# Voltage_AC.net
KiCad netlist of a schematic drawn in Altium Designer
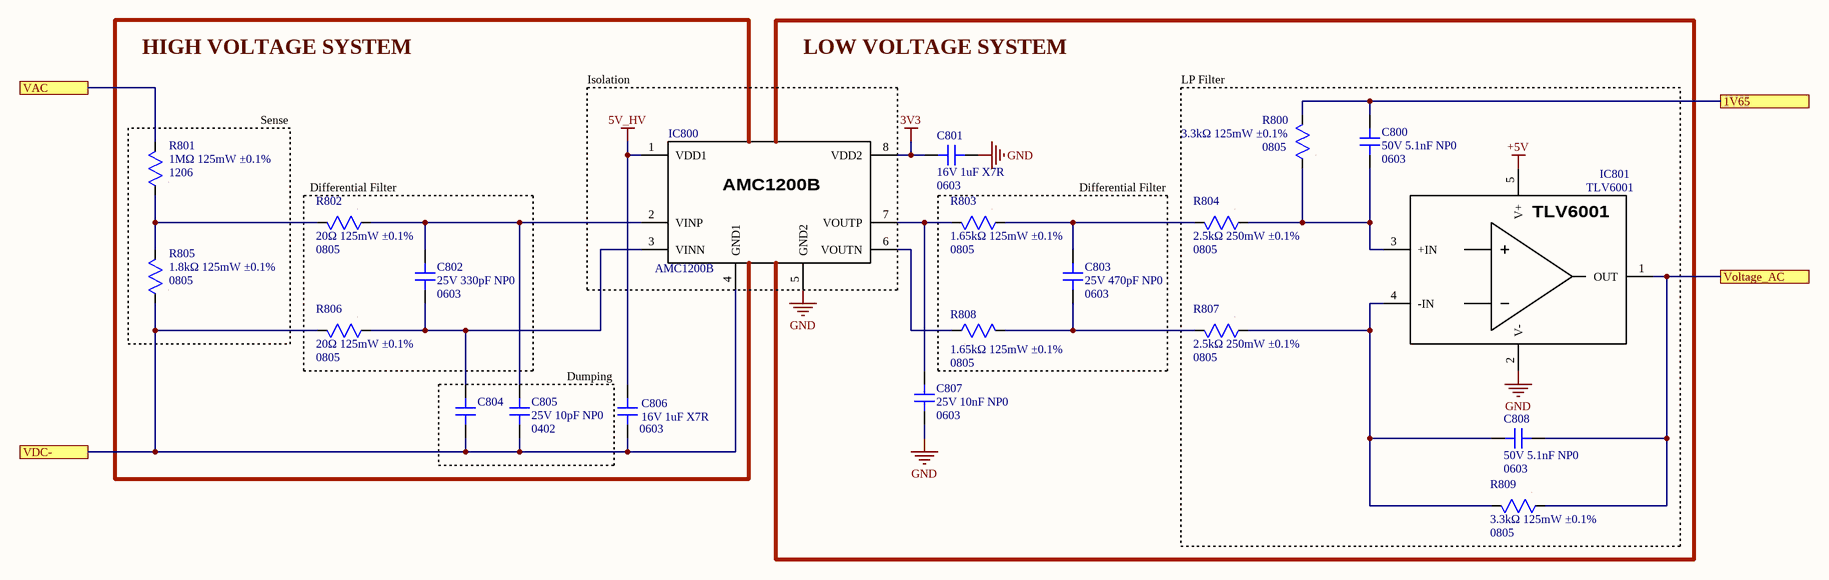
[diagram p0: Voltage_AC.SchDoc]

(export (version "E")
  (design (tool "Eeschema 10.0.6"))
  (components
    (comp (ref "C800")
      (value "50V 5.1nF NP0")
      (footprint "CAP SMD 0603")
      (description "Condensadores de cerámica multicapa (MLCC- SMD/SMT) 50V 5100pF 0603 C0G 1%")
      (fields
        (field (name "PACKAGE") "0603")
        (field (name "MPN") "C0603C512F5GACTU")
        (field (name "MANUFACTURER") "KEMET")
      )
      (libsource (lib "eUSR_Database") (part "CAP non polarized"))
    )
    (comp (ref "C801")
      (value "16V 1uF X7R")
      (footprint "CAP SMD 0603")
      (description "Condensadores de cerámica multicapa (MLCC- SMD/SMT) WCAP-CSGP 1uF 0603 10% 16V MLCC")
      (fields
        (field (name "PACKAGE") "0603")
        (field (name "MPN") "885012206052")
        (field (name "MANUFACTURER") "Wurth Elektronik")
      )
      (libsource (lib "eUSR_Database") (part "CAP non polarized"))
    )
    (comp (ref "C802")
      (value "25V 330pF NP0")
      (footprint "CAP SMD 0603")
      (description "Condensadores de cerámica multicapa (MLCC- SMD/SMT) 0603 330pF 25volts C0G 1%")
      (fields
        (field (name "PACKAGE") "0603")
        (field (name "MPN") "VJ0603A331FXXCW1BC")
        (field (name "MANUFACTURER") "Vishay")
      )
      (libsource (lib "eUSR_Database") (part "CAP non polarized"))
    )
    (comp (ref "C803")
      (value "25V 470pF NP0")
      (footprint "CAP SMD 0603")
      (fields
        (field (name "PACKAGE") "0603")
        (field (name "MPN") "VJ0603D471KCXAJ")
        (field (name "MANUFACTURER") "Vishay")
        (field (name "Comment") "CAP non polarized")
      )
      (libsource (lib "eUSR_Database") (part "CAP non polarized"))
    )
    (comp (ref "C804")
      (value "CAP non polarized")
      (footprint "CAP SMD 0402")
      (description "Condensadores de cerámica multicapa (MLCC- SMD/SMT) 25V 10pF C0G 0402 0. 1pF")
      (fields (field (name "MPN") "04023A100BAT2A") (field (name "MANUFACTURER") "KYOCERA AVX"))
      (libsource (lib "eUSR_Database") (part "CAP non polarized"))
    )
    (comp (ref "C805")
      (value "25V 10pF NP0")
      (footprint "CAP SMD 0402")
      (description "Condensadores de cerámica multicapa (MLCC- SMD/SMT) 25V 10pF C0G 0402 0. 1pF")
      (fields
        (field (name "PACKAGE") "0402")
        (field (name "MPN") "04023A100BAT2A")
        (field (name "MANUFACTURER") "KYOCERA AVX")
      )
      (libsource (lib "eUSR_Database") (part "CAP non polarized"))
    )
    (comp (ref "C806")
      (value "16V 1uF X7R")
      (footprint "CAP SMD 0603")
      (description "Condensadores de cerámica multicapa (MLCC- SMD/SMT) WCAP-CSGP 1uF 0603 10% 16V MLCC")
      (fields
        (field (name "PACKAGE") "0603")
        (field (name "MPN") "885012206052")
        (field (name "MANUFACTURER") "Wurth Elektronik")
      )
      (libsource (lib "eUSR_Database") (part "CAP non polarized"))
    )
    (comp (ref "C807")
      (value "25V 10nF NP0")
      (footprint "CAP SMD 0603")
      (description "Condensadores de cerámica multicapa (MLCC- SMD/SMT) 50V 5100pF 0603 C0G 1%")
      (fields
        (field (name "PACKAGE") "0603")
        (field (name "MPN") "C0603C512F5GACTU")
        (field (name "MANUFACTURER") "KEMET")
      )
      (libsource (lib "eUSR_Database") (part "CAP non polarized"))
    )
    (comp (ref "C808")
      (value "50V 5.1nF NP0")
      (footprint "CAP SMD 0603")
      (description "Condensadores de cerámica multicapa (MLCC- SMD/SMT) 50V 5100pF 0603 C0G 1%")
      (fields
        (field (name "PACKAGE") "0603")
        (field (name "MPN") "C0603C512F5GACTU")
        (field (name "MANUFACTURER") "KEMET")
      )
      (libsource (lib "eUSR_Database") (part "CAP non polarized"))
    )
    (comp (ref "IC800")
      (value "AMC1200B")
      (footprint "AMC1200B")
      (description "Amplificadores de aislamiento 4kV peak Iso Amp A 5 95-AMC1200BDUB A 59 A 595-AMC1200BDUB")
      (fields (field (name "MPN") "AMC1200BDUBR") (field (name "MANUFACTURER") "Texas Instruments"))
      (libsource (lib "eUSR_Database") (part "AMC1200B"))
    )
    (comp (ref "IC801")
      (value "TLV6001")
      (footprint "SOT-23-5")
      (fields (field (name "MPN") "TLV6001UIDBVR") (field (name "MANUFACTURER") "Texas Instruments"))
      (libsource (lib "eUSR_Database") (part "TLV6001"))
    )
    (comp (ref "R800")
      (value "3.3kΩ 125mW ±0.1%")
      (footprint "RES SMD 0805")
      (description "Thin Film Resistors 0805 3.3Kohm 0.1% 15ppm AEC-Q200")
      (fields
        (field (name "PACKAGE") "0805")
        (field (name "MPN") "ERA-6APB332V")
        (field (name "MANUFACTURER") "Panasonic")
      )
      (libsource (lib "eUSR_Database") (part "RES"))
    )
    (comp (ref "R801")
      (value "1MΩ 125mW ±0.1%")
      (footprint "RES SMD 1206")
      (description "Thin Film Resistors CHIP RESISTOR Precision")
      (fields
        (field (name "PACKAGE") "1206")
        (field (name "MPN") "CRT1206-BW-1004ELF")
        (field (name "MANUFACTURER") "Bourns")
      )
      (libsource (lib "eUSR_Database") (part "RES"))
    )
    (comp (ref "R802")
      (value "20Ω 125mW ±0.1%")
      (footprint "RES SMD 0805")
      (description "Thin Film Resistors RP 2A 20R 0.1% 15PPM CUT LENGTH")
      (fields
        (field (name "PACKAGE") "0805")
        (field (name "MPN") "RP73D2A20RBTG")
        (field (name "MANUFACTURER") "TE")
      )
      (libsource (lib "eUSR_Database") (part "RES"))
    )
    (comp (ref "R803")
      (value "1.65kΩ 125mW ±0.1%")
      (footprint "RES SMD 0805")
      (description "Thin Film Resistors MCU 0805-15 0.1% P1 1K65")
      (fields
        (field (name "PACKAGE") "0805")
        (field (name "MPN") "MCU08050E1651BP100")
        (field (name "MANUFACTURER") "Vishay")
      )
      (libsource (lib "eUSR_Database") (part "RES"))
    )
    (comp (ref "R804")
      (value "2.5kΩ 250mW ±0.1%")
      (footprint "RES SMD 0805")
      (description "Thin Film Resistors 2.5K OHM .1% 25PPM 1/4W")
      (fields
        (field (name "PACKAGE") "0805")
        (field (name "MPN") "RN73R2ATTD2501B25")
        (field (name "MANUFACTURER") "KOA Speer")
      )
      (libsource (lib "eUSR_Database") (part "RES"))
    )
    (comp (ref "R805")
      (value "1.8kΩ 125mW ±0.1%")
      (footprint "RES SMD 0805")
      (description "Thin Film Resistors 0805 1.8Kohm 0.1% 10ppm AEC-Q200")
      (fields
        (field (name "PACKAGE") "0805")
        (field (name "MPN") "ERA-6ARB182V")
        (field (name "MANUFACTURER") "Panasonic")
      )
      (libsource (lib "eUSR_Database") (part "RES"))
    )
    (comp (ref "R806")
      (value "20Ω 125mW ±0.1%")
      (footprint "RES SMD 0805")
      (description "Thin Film Resistors RP 2A 20R 0.1% 15PPM CUT LENGTH")
      (fields
        (field (name "PACKAGE") "0805")
        (field (name "MPN") "RP73D2A20RBTG")
        (field (name "MANUFACTURER") "TE")
      )
      (libsource (lib "eUSR_Database") (part "RES"))
    )
    (comp (ref "R807")
      (value "2.5kΩ 250mW ±0.1%")
      (footprint "RES SMD 0805")
      (description "Thin Film Resistors 2.5K OHM .1% 25PPM 1/4W")
      (fields
        (field (name "PACKAGE") "0805")
        (field (name "MPN") "RN73R2ATTD2501B25")
        (field (name "MANUFACTURER") "KOA Speer")
      )
      (libsource (lib "eUSR_Database") (part "RES"))
    )
    (comp (ref "R808")
      (value "1.65kΩ 125mW ±0.1%")
      (footprint "RES SMD 0805")
      (description "Thin Film Resistors MCU 0805-15 0.1% P1 1K65")
      (fields
        (field (name "PACKAGE") "0805")
        (field (name "MPN") "MCU08050E1651BP100")
        (field (name "MANUFACTURER") "Vishay")
      )
      (libsource (lib "eUSR_Database") (part "RES"))
    )
    (comp (ref "R809")
      (value "3.3kΩ 125mW ±0.1%")
      (footprint "RES SMD 0805")
      (description "Thin Film Resistors 0805 3.3Kohm 0.1% 15ppm AEC-Q200")
      (fields
        (field (name "PACKAGE") "0805")
        (field (name "MPN") "ERA-6APB332V")
        (field (name "MANUFACTURER") "Panasonic")
      )
      (libsource (lib "eUSR_Database") (part "RES"))
    )
  )
  (nets
    (net (code "1") (name "+5V") (class "Default")
      (node (ref "IC801") (pin "5") (pinfunction "V+_5") (pintype "passive"))
    )
    (net (code "2") (name "/1V65") (class "Default")
      (node (ref "C800") (pin "1") (pinfunction "1_1") (pintype "passive"))
      (node (ref "R800") (pin "2") (pinfunction "2_2") (pintype "passive"))
    )
    (net (code "3") (name "/VAC") (class "Default")
      (node (ref "R801") (pin "2") (pinfunction "2_2") (pintype "passive"))
    )
    (net (code "4") (name "/VDC-") (class "Default")
      (node (ref "C804") (pin "2") (pinfunction "2_2") (pintype "passive"))
      (node (ref "C805") (pin "2") (pinfunction "2_2") (pintype "passive"))
      (node (ref "C806") (pin "2") (pinfunction "2_2") (pintype "passive"))
      (node (ref "IC800") (pin "4") (pinfunction "GND1_4") (pintype "passive"))
      (node (ref "R805") (pin "1") (pinfunction "1_1") (pintype "passive"))
      (node (ref "R806") (pin "2") (pinfunction "2_2") (pintype "passive"))
    )
    (net (code "5") (name "/Voltage_AC") (class "Default")
      (node (ref "C808") (pin "2") (pinfunction "2_2") (pintype "passive"))
      (node (ref "IC801") (pin "1") (pinfunction "OUT_1") (pintype "passive"))
      (node (ref "R809") (pin "1") (pinfunction "1_1") (pintype "passive"))
    )
    (net (code "6") (name "3V3") (class "Default")
      (node (ref "C801") (pin "1") (pinfunction "1_1") (pintype "passive"))
      (node (ref "IC800") (pin "8") (pinfunction "VDD2_8") (pintype "passive"))
    )
    (net (code "7") (name "5V_HV") (class "Default")
      (node (ref "C806") (pin "1") (pinfunction "1_1") (pintype "passive"))
      (node (ref "IC800") (pin "1") (pinfunction "VDD1_1") (pintype "passive"))
    )
    (net (code "8") (name "GND") (class "Default")
      (node (ref "C801") (pin "2") (pinfunction "2_2") (pintype "passive"))
      (node (ref "C807") (pin "2") (pinfunction "2_2") (pintype "passive"))
      (node (ref "IC800") (pin "5") (pinfunction "GND2_5") (pintype "passive"))
      (node (ref "IC801") (pin "2") (pinfunction "V-_2") (pintype "passive"))
    )
    (net (code "9") (name "Net-(C803-Pad1)") (class "Default")
      (node (ref "C803") (pin "1") (pinfunction "1_1") (pintype "passive"))
      (node (ref "R803") (pin "1") (pinfunction "1_1") (pintype "passive"))
      (node (ref "R804") (pin "2") (pinfunction "2_2") (pintype "passive"))
    )
    (net (code "10") (name "Net-(C803-Pad2)") (class "Default")
      (node (ref "C803") (pin "2") (pinfunction "2_2") (pintype "passive"))
      (node (ref "R807") (pin "2") (pinfunction "2_2") (pintype "passive"))
      (node (ref "R808") (pin "2") (pinfunction "2_2") (pintype "passive"))
    )
    (net (code "11") (name "Net-(IC800-VINN)") (class "Default")
      (node (ref "C802") (pin "2") (pinfunction "2_2") (pintype "passive"))
      (node (ref "C804") (pin "1") (pinfunction "1_1") (pintype "passive"))
      (node (ref "IC800") (pin "3") (pinfunction "VINN_3") (pintype "passive"))
      (node (ref "R806") (pin "1") (pinfunction "1_1") (pintype "passive"))
    )
    (net (code "12") (name "Net-(IC800-VINP)") (class "Default")
      (node (ref "C802") (pin "1") (pinfunction "1_1") (pintype "passive"))
      (node (ref "C805") (pin "1") (pinfunction "1_1") (pintype "passive"))
      (node (ref "IC800") (pin "2") (pinfunction "VINP_2") (pintype "passive"))
      (node (ref "R802") (pin "1") (pinfunction "1_1") (pintype "passive"))
    )
    (net (code "13") (name "Net-(IC800-VOUTN)") (class "Default")
      (node (ref "IC800") (pin "6") (pinfunction "VOUTN_6") (pintype "passive"))
      (node (ref "R808") (pin "1") (pinfunction "1_1") (pintype "passive"))
    )
    (net (code "14") (name "Net-(IC800-VOUTP)") (class "Default")
      (node (ref "C807") (pin "1") (pinfunction "1_1") (pintype "passive"))
      (node (ref "IC800") (pin "7") (pinfunction "VOUTP_7") (pintype "passive"))
      (node (ref "R803") (pin "2") (pinfunction "2_2") (pintype "passive"))
    )
    (net (code "15") (name "Net-(IC801-+IN)") (class "Default")
      (node (ref "C800") (pin "2") (pinfunction "2_2") (pintype "passive"))
      (node (ref "IC801") (pin "3") (pinfunction "+IN_3") (pintype "passive"))
      (node (ref "R800") (pin "1") (pinfunction "1_1") (pintype "passive"))
      (node (ref "R804") (pin "1") (pinfunction "1_1") (pintype "passive"))
    )
    (net (code "16") (name "Net-(IC801--IN)") (class "Default")
      (node (ref "C808") (pin "1") (pinfunction "1_1") (pintype "passive"))
      (node (ref "IC801") (pin "4") (pinfunction "-IN_4") (pintype "passive"))
      (node (ref "R807") (pin "1") (pinfunction "1_1") (pintype "passive"))
      (node (ref "R809") (pin "2") (pinfunction "2_2") (pintype "passive"))
    )
    (net (code "17") (name "Net-(R801-Pad1)") (class "Default")
      (node (ref "R801") (pin "1") (pinfunction "1_1") (pintype "passive"))
      (node (ref "R802") (pin "2") (pinfunction "2_2") (pintype "passive"))
      (node (ref "R805") (pin "2") (pinfunction "2_2") (pintype "passive"))
    )
  )
)
